# MOSFET_Driver_Sheet2.net
KiCad netlist of a schematic drawn in Altium Designer
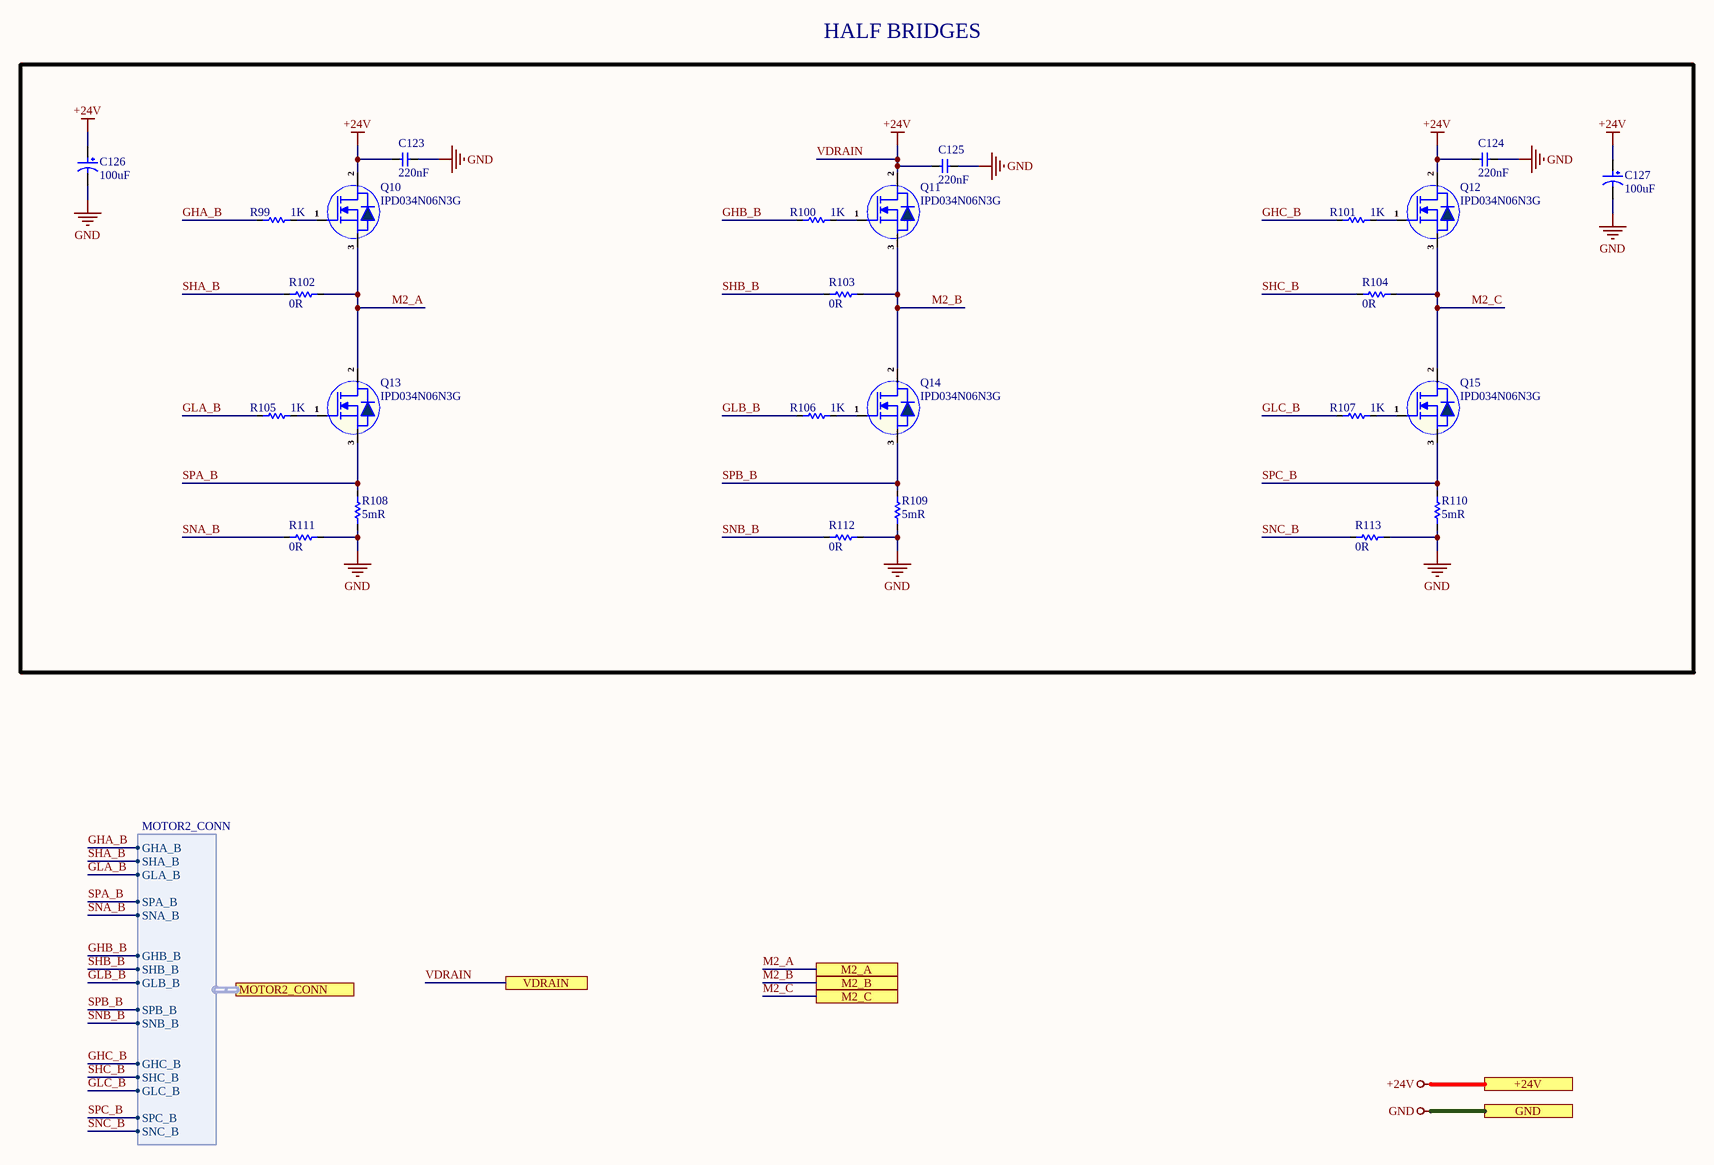
[diagram p0: MOSFET_Driver_Sheet2.SchDoc]

(export (version "E")
  (design (tool "Eeschema 10.0.6"))
  (components
    (comp (ref "C123")
      (value "220nF")
      (footprint "Cap-0805")
      (description "CAP CER 0.22UF 100V X7R 0805")
      (fields
        (field (name "MANUFACTURER") "Kyocera AVX")
        (field (name "MANUFACTURER PART NUMBER") "08051C224K4T2A")
      )
      (libsource (lib "eSpark Libraries") (part "08051C224K4T2A"))
    )
    (comp (ref "C124")
      (value "220nF")
      (footprint "Cap-0805")
      (description "CAP CER 0.22UF 100V X7R 0805")
      (fields
        (field (name "MANUFACTURER") "Kyocera AVX")
        (field (name "MANUFACTURER PART NUMBER") "08051C224K4T2A")
      )
      (libsource (lib "eSpark Libraries") (part "08051C224K4T2A"))
    )
    (comp (ref "C125")
      (value "220nF")
      (footprint "Cap-0805")
      (description "CAP CER 0.22UF 100V X7R 0805")
      (fields
        (field (name "MANUFACTURER") "Kyocera AVX")
        (field (name "MANUFACTURER PART NUMBER") "08051C224K4T2A")
      )
      (libsource (lib "eSpark Libraries") (part "08051C224K4T2A"))
    )
    (comp (ref "C126")
      (value "100uF")
      (footprint "RVT1A101M0605")
      (description "100uF 10V 55mA@120Hz ±20% SMD,D6.3xL5.4mm Aluminum Electrolytic Capacitors - SMD ROHS")
      (fields
        (field (name "MANUFACTURER") "ROQANG")
        (field (name "MANUFACTURER PART NUMBER") "RVT1A101M0605")
      )
      (libsource (lib "eSpark Libraries") (part "RVT1A101M0605"))
    )
    (comp (ref "C127")
      (value "100uF")
      (footprint "RVT1A101M0605")
      (description "100uF 10V 55mA@120Hz ±20% SMD,D6.3xL5.4mm Aluminum Electrolytic Capacitors - SMD ROHS")
      (fields
        (field (name "MANUFACTURER") "ROQANG")
        (field (name "MANUFACTURER PART NUMBER") "RVT1A101M0605")
      )
      (libsource (lib "eSpark Libraries") (part "RVT1A101M0605"))
    )
    (comp (ref "Q10")
      (value "IPD034N06N3G")
      (footprint "TO-252-2L")
      (description "MOSFET N-CH 60V 100A TO252-3")
      (fields (field (name "MANUFACTURER") "Infineon") (field (name "LCSC PART NUMBER") "C94897"))
      (libsource (lib "eSpark Libraries") (part "IPD034N06N3G"))
    )
    (comp (ref "Q11")
      (value "IPD034N06N3G")
      (footprint "TO-252-2L")
      (description "MOSFET N-CH 60V 100A TO252-3")
      (fields (field (name "MANUFACTURER") "Infineon") (field (name "LCSC PART NUMBER") "C94897"))
      (libsource (lib "eSpark Libraries") (part "IPD034N06N3G"))
    )
    (comp (ref "Q12")
      (value "IPD034N06N3G")
      (footprint "TO-252-2L")
      (description "MOSFET N-CH 60V 100A TO252-3")
      (fields (field (name "MANUFACTURER") "Infineon") (field (name "LCSC PART NUMBER") "C94897"))
      (libsource (lib "eSpark Libraries") (part "IPD034N06N3G"))
    )
    (comp (ref "Q13")
      (value "IPD034N06N3G")
      (footprint "TO-252-2L")
      (description "MOSFET N-CH 60V 100A TO252-3")
      (fields (field (name "MANUFACTURER") "Infineon") (field (name "LCSC PART NUMBER") "C94897"))
      (libsource (lib "eSpark Libraries") (part "IPD034N06N3G"))
    )
    (comp (ref "Q14")
      (value "IPD034N06N3G")
      (footprint "TO-252-2L")
      (description "MOSFET N-CH 60V 100A TO252-3")
      (fields (field (name "MANUFACTURER") "Infineon") (field (name "LCSC PART NUMBER") "C94897"))
      (libsource (lib "eSpark Libraries") (part "IPD034N06N3G"))
    )
    (comp (ref "Q15")
      (value "IPD034N06N3G")
      (footprint "TO-252-2L")
      (description "MOSFET N-CH 60V 100A TO252-3")
      (fields (field (name "MANUFACTURER") "Infineon") (field (name "LCSC PART NUMBER") "C94897"))
      (libsource (lib "eSpark Libraries") (part "IPD034N06N3G"))
    )
    (comp (ref "R99")
      (value "1K")
      (footprint "Res-0402")
      (description "RES 1K OHM 1% 1/16W 0402")
      (fields
        (field (name "MANUFACTURER") "Yageo")
        (field (name "MANUFACTURER PART NUMBER") "RC0402FR-071KL")
      )
      (libsource (lib "eSpark Libraries") (part "RC0402FR-071KL"))
    )
    (comp (ref "R100")
      (value "1K")
      (footprint "Res-0402")
      (description "RES 1K OHM 1% 1/16W 0402")
      (fields
        (field (name "MANUFACTURER") "Yageo")
        (field (name "MANUFACTURER PART NUMBER") "RC0402FR-071KL")
      )
      (libsource (lib "eSpark Libraries") (part "RC0402FR-071KL"))
    )
    (comp (ref "R101")
      (value "1K")
      (footprint "Res-0402")
      (description "RES 1K OHM 1% 1/16W 0402")
      (fields
        (field (name "MANUFACTURER") "Yageo")
        (field (name "MANUFACTURER PART NUMBER") "RC0402FR-071KL")
      )
      (libsource (lib "eSpark Libraries") (part "RC0402FR-071KL"))
    )
    (comp (ref "R102")
      (value "0R")
      (footprint "Res-0603")
      (description "RES 0 OHM JUMPER 1/10W 0603")
      (fields
        (field (name "MANUFACTURER") "Yageo")
        (field (name "MANUFACTURER PART NUMBER") "RC0603JR-070RL")
      )
      (libsource (lib "eSpark Libraries") (part "RC0603JR-070RL"))
    )
    (comp (ref "R103")
      (value "0R")
      (footprint "Res-0603")
      (description "RES 0 OHM JUMPER 1/10W 0603")
      (fields
        (field (name "MANUFACTURER") "Yageo")
        (field (name "MANUFACTURER PART NUMBER") "RC0603JR-070RL")
      )
      (libsource (lib "eSpark Libraries") (part "RC0603JR-070RL"))
    )
    (comp (ref "R104")
      (value "0R")
      (footprint "Res-0603")
      (description "RES 0 OHM JUMPER 1/10W 0603")
      (fields
        (field (name "MANUFACTURER") "Yageo")
        (field (name "MANUFACTURER PART NUMBER") "RC0603JR-070RL")
      )
      (libsource (lib "eSpark Libraries") (part "RC0603JR-070RL"))
    )
    (comp (ref "R105")
      (value "1K")
      (footprint "Res-0402")
      (description "RES 1K OHM 1% 1/16W 0402")
      (fields
        (field (name "MANUFACTURER") "Yageo")
        (field (name "MANUFACTURER PART NUMBER") "RC0402FR-071KL")
      )
      (libsource (lib "eSpark Libraries") (part "RC0402FR-071KL"))
    )
    (comp (ref "R106")
      (value "1K")
      (footprint "Res-0402")
      (description "RES 1K OHM 1% 1/16W 0402")
      (fields
        (field (name "MANUFACTURER") "Yageo")
        (field (name "MANUFACTURER PART NUMBER") "RC0402FR-071KL")
      )
      (libsource (lib "eSpark Libraries") (part "RC0402FR-071KL"))
    )
    (comp (ref "R107")
      (value "1K")
      (footprint "Res-0402")
      (description "RES 1K OHM 1% 1/16W 0402")
      (fields
        (field (name "MANUFACTURER") "Yageo")
        (field (name "MANUFACTURER PART NUMBER") "RC0402FR-071KL")
      )
      (libsource (lib "eSpark Libraries") (part "RC0402FR-071KL"))
    )
    (comp (ref "R108")
      (value "5mR")
      (footprint "Res-1206")
      (description "1W 5mΩ ±1% 1206 Current Sense Resistors/Shunt Resistors ROHS")
      (fields
        (field (name "MANUFACTURER") "FORT")
        (field (name "MANUFACTURER PART NUMBER") "CUM1206-15FR005")
      )
      (libsource (lib "eSpark Libraries") (part "CUM1206-15FR005"))
    )
    (comp (ref "R109")
      (value "5mR")
      (footprint "Res-1206")
      (description "1W 5mΩ ±1% 1206 Current Sense Resistors/Shunt Resistors ROHS")
      (fields
        (field (name "MANUFACTURER") "FORT")
        (field (name "MANUFACTURER PART NUMBER") "CUM1206-15FR005")
      )
      (libsource (lib "eSpark Libraries") (part "CUM1206-15FR005"))
    )
    (comp (ref "R110")
      (value "5mR")
      (footprint "Res-1206")
      (description "1W 5mΩ ±1% 1206 Current Sense Resistors/Shunt Resistors ROHS")
      (fields
        (field (name "MANUFACTURER") "FORT")
        (field (name "MANUFACTURER PART NUMBER") "CUM1206-15FR005")
      )
      (libsource (lib "eSpark Libraries") (part "CUM1206-15FR005"))
    )
    (comp (ref "R111")
      (value "0R")
      (footprint "Res-0603")
      (description "RES 0 OHM JUMPER 1/10W 0603")
      (fields
        (field (name "MANUFACTURER") "Yageo")
        (field (name "MANUFACTURER PART NUMBER") "RC0603JR-070RL")
      )
      (libsource (lib "eSpark Libraries") (part "RC0603JR-070RL"))
    )
    (comp (ref "R112")
      (value "0R")
      (footprint "Res-0603")
      (description "RES 0 OHM JUMPER 1/10W 0603")
      (fields
        (field (name "MANUFACTURER") "Yageo")
        (field (name "MANUFACTURER PART NUMBER") "RC0603JR-070RL")
      )
      (libsource (lib "eSpark Libraries") (part "RC0603JR-070RL"))
    )
    (comp (ref "R113")
      (value "0R")
      (footprint "Res-0603")
      (description "RES 0 OHM JUMPER 1/10W 0603")
      (fields
        (field (name "MANUFACTURER") "Yageo")
        (field (name "MANUFACTURER PART NUMBER") "RC0603JR-070RL")
      )
      (libsource (lib "eSpark Libraries") (part "RC0603JR-070RL"))
    )
  )
  (nets
    (net (code "2") (name "+24V") (class "Default")
      (node (ref "C123") (pin "2") (pinfunction "2_2") (pintype "passive"))
      (node (ref "C124") (pin "2") (pinfunction "2_2") (pintype "passive"))
      (node (ref "C125") (pin "2") (pinfunction "2_2") (pintype "passive"))
      (node (ref "C126") (pin "1") (pintype "passive"))
      (node (ref "C127") (pin "1") (pintype "passive"))
      (node (ref "Q10") (pin "2") (pinfunction "D_2") (pintype "passive"))
      (node (ref "Q11") (pin "2") (pinfunction "D_2") (pintype "passive"))
      (node (ref "Q12") (pin "2") (pinfunction "D_2") (pintype "passive"))
    )
    (net (code "3") (name "/GHA_B") (class "Default")
      (node (ref "R99") (pin "1") (pinfunction "1_1") (pintype "passive"))
    )
    (net (code "4") (name "/GHB_B") (class "Default")
      (node (ref "R100") (pin "1") (pinfunction "1_1") (pintype "passive"))
    )
    (net (code "5") (name "/GHC_B") (class "Default")
      (node (ref "R101") (pin "1") (pinfunction "1_1") (pintype "passive"))
    )
    (net (code "6") (name "/GLA_B") (class "Default")
      (node (ref "R105") (pin "1") (pinfunction "1_1") (pintype "passive"))
    )
    (net (code "7") (name "/GLB_B") (class "Default")
      (node (ref "R106") (pin "1") (pinfunction "1_1") (pintype "passive"))
    )
    (net (code "8") (name "/GLC_B") (class "Default")
      (node (ref "R107") (pin "1") (pinfunction "1_1") (pintype "passive"))
    )
    (net (code "9") (name "/M2_A") (class "Default")
      (node (ref "Q10") (pin "3") (pinfunction "S_3") (pintype "passive"))
      (node (ref "Q13") (pin "2") (pinfunction "D_2") (pintype "passive"))
      (node (ref "R102") (pin "1") (pinfunction "1_1") (pintype "passive"))
    )
    (net (code "10") (name "/M2_B") (class "Default")
      (node (ref "Q11") (pin "3") (pinfunction "S_3") (pintype "passive"))
      (node (ref "Q14") (pin "2") (pinfunction "D_2") (pintype "passive"))
      (node (ref "R103") (pin "1") (pinfunction "1_1") (pintype "passive"))
    )
    (net (code "11") (name "/M2_C") (class "Default")
      (node (ref "Q12") (pin "3") (pinfunction "S_3") (pintype "passive"))
      (node (ref "Q15") (pin "2") (pinfunction "D_2") (pintype "passive"))
      (node (ref "R104") (pin "1") (pinfunction "1_1") (pintype "passive"))
    )
    (net (code "12") (name "/SHA_B") (class "Default")
      (node (ref "R102") (pin "2") (pinfunction "2_2") (pintype "passive"))
    )
    (net (code "13") (name "/SHB_B") (class "Default")
      (node (ref "R103") (pin "2") (pinfunction "2_2") (pintype "passive"))
    )
    (net (code "14") (name "/SHC_B") (class "Default")
      (node (ref "R104") (pin "2") (pinfunction "2_2") (pintype "passive"))
    )
    (net (code "15") (name "/SNA_B") (class "Default")
      (node (ref "R111") (pin "2") (pinfunction "2_2") (pintype "passive"))
    )
    (net (code "16") (name "/SNB_B") (class "Default")
      (node (ref "R112") (pin "2") (pinfunction "2_2") (pintype "passive"))
    )
    (net (code "17") (name "/SNC_B") (class "Default")
      (node (ref "R113") (pin "2") (pinfunction "2_2") (pintype "passive"))
    )
    (net (code "18") (name "/SPA_B") (class "Default")
      (node (ref "Q13") (pin "3") (pinfunction "S_3") (pintype "passive"))
      (node (ref "R108") (pin "2") (pinfunction "2_2") (pintype "passive"))
    )
    (net (code "19") (name "/SPB_B") (class "Default")
      (node (ref "Q14") (pin "3") (pinfunction "S_3") (pintype "passive"))
      (node (ref "R109") (pin "2") (pinfunction "2_2") (pintype "passive"))
    )
    (net (code "20") (name "/SPC_B") (class "Default")
      (node (ref "Q15") (pin "3") (pinfunction "S_3") (pintype "passive"))
      (node (ref "R110") (pin "2") (pinfunction "2_2") (pintype "passive"))
    )
    (net (code "22") (name "GND") (class "Default")
      (node (ref "C123") (pin "1") (pinfunction "1_1") (pintype "passive"))
      (node (ref "C124") (pin "1") (pinfunction "1_1") (pintype "passive"))
      (node (ref "C125") (pin "1") (pinfunction "1_1") (pintype "passive"))
      (node (ref "C126") (pin "2") (pintype "passive"))
      (node (ref "C127") (pin "2") (pintype "passive"))
      (node (ref "R108") (pin "1") (pinfunction "1_1") (pintype "passive"))
      (node (ref "R109") (pin "1") (pinfunction "1_1") (pintype "passive"))
      (node (ref "R110") (pin "1") (pinfunction "1_1") (pintype "passive"))
      (node (ref "R111") (pin "1") (pinfunction "1_1") (pintype "passive"))
      (node (ref "R112") (pin "1") (pinfunction "1_1") (pintype "passive"))
      (node (ref "R113") (pin "1") (pinfunction "1_1") (pintype "passive"))
    )
    (net (code "23") (name "Net-(Q10-G)") (class "Default")
      (node (ref "Q10") (pin "1") (pinfunction "G_1") (pintype "passive"))
      (node (ref "R99") (pin "2") (pinfunction "2_2") (pintype "passive"))
    )
    (net (code "24") (name "Net-(Q11-G)") (class "Default")
      (node (ref "Q11") (pin "1") (pinfunction "G_1") (pintype "passive"))
      (node (ref "R100") (pin "2") (pinfunction "2_2") (pintype "passive"))
    )
    (net (code "25") (name "Net-(Q12-G)") (class "Default")
      (node (ref "Q12") (pin "1") (pinfunction "G_1") (pintype "passive"))
      (node (ref "R101") (pin "2") (pinfunction "2_2") (pintype "passive"))
    )
    (net (code "26") (name "Net-(Q13-G)") (class "Default")
      (node (ref "Q13") (pin "1") (pinfunction "G_1") (pintype "passive"))
      (node (ref "R105") (pin "2") (pinfunction "2_2") (pintype "passive"))
    )
    (net (code "27") (name "Net-(Q14-G)") (class "Default")
      (node (ref "Q14") (pin "1") (pinfunction "G_1") (pintype "passive"))
      (node (ref "R106") (pin "2") (pinfunction "2_2") (pintype "passive"))
    )
    (net (code "28") (name "Net-(Q15-G)") (class "Default")
      (node (ref "Q15") (pin "1") (pinfunction "G_1") (pintype "passive"))
      (node (ref "R107") (pin "2") (pinfunction "2_2") (pintype "passive"))
    )
  )
)
